# sensor_node4.net
KiCad netlist of a schematic drawn in EAGLE
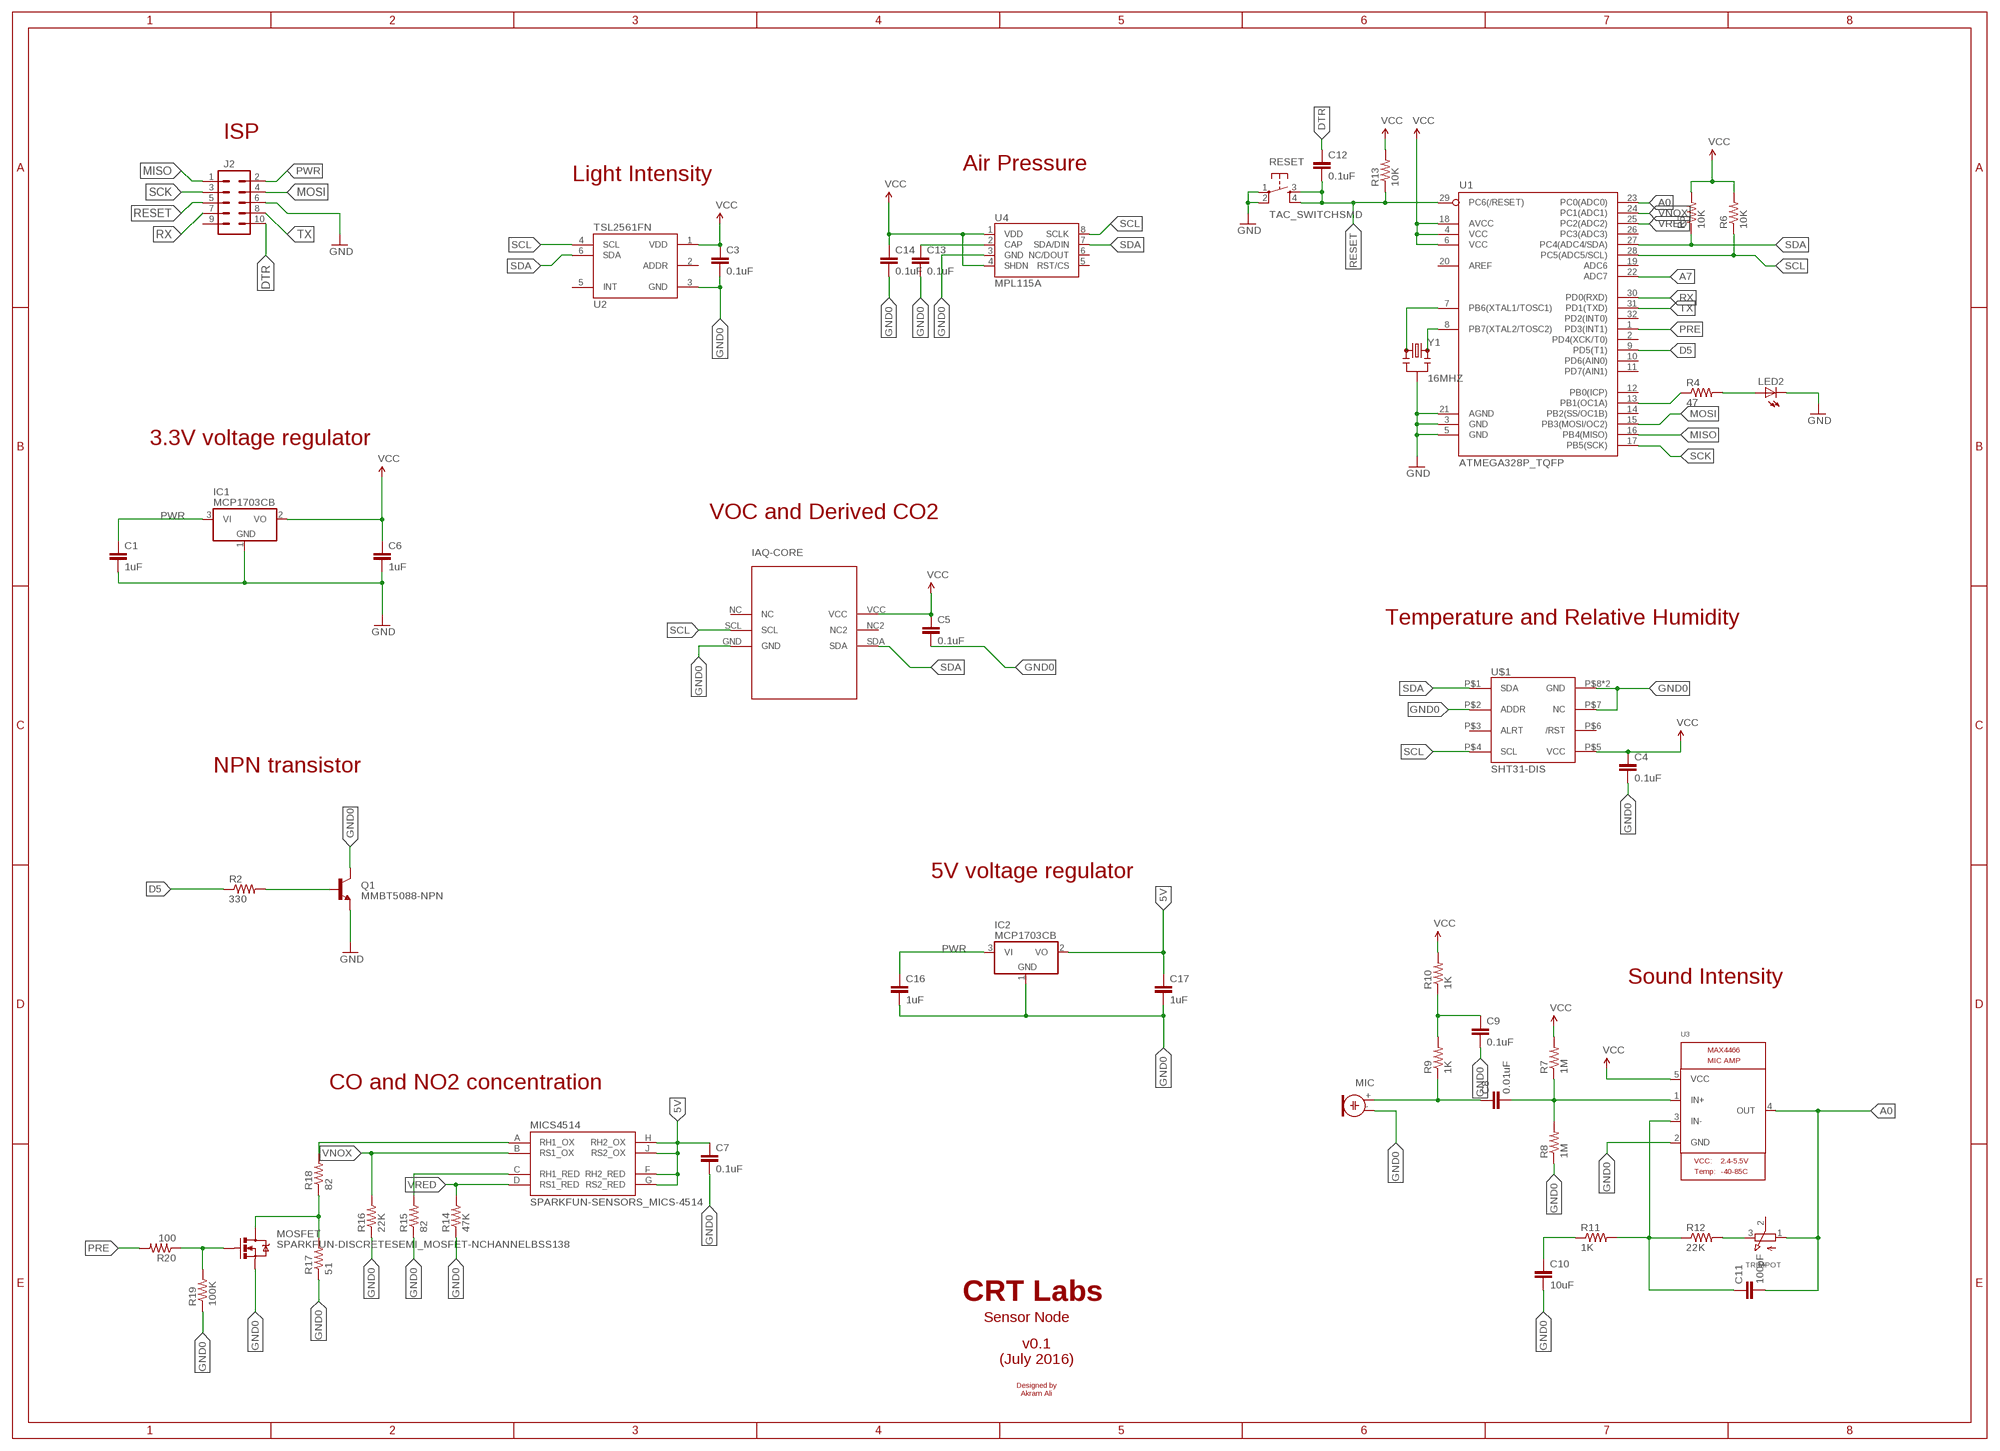
[diagram p0: schematic, sheet 1]

(export (version "E")
  (design (tool "Eeschema 10.0.6"))
  (components
    (comp (ref "C1")
      (value "1uF")
      (footprint "eagle-import:0805")
      (libsource (lib "eagle-import") (part "CAP0805"))
    )
    (comp (ref "C3")
      (value "0.1uF")
      (footprint "eagle-import:0805")
      (libsource (lib "eagle-import") (part "SparkFun-Passives_CAP0805"))
    )
    (comp (ref "C4")
      (value "0.1uF")
      (footprint "eagle-import:0805")
      (libsource (lib "eagle-import") (part "SparkFun-Passives_CAP0805"))
    )
    (comp (ref "C5")
      (value "0.1uF")
      (footprint "eagle-import:0805")
      (libsource (lib "eagle-import") (part "SparkFun-Passives_CAP0805"))
    )
    (comp (ref "C6")
      (value "1uF")
      (footprint "eagle-import:0805")
      (libsource (lib "eagle-import") (part "CAP0805"))
    )
    (comp (ref "C7")
      (value "0.1uF")
      (footprint "eagle-import:0805")
      (libsource (lib "eagle-import") (part "SparkFun-Passives_CAP0805"))
    )
    (comp (ref "C8")
      (value "0.01uF")
      (footprint "eagle-import:0805")
      (libsource (lib "eagle-import") (part "SparkFun-Passives_CAP0805"))
    )
    (comp (ref "C9")
      (value "0.1uF")
      (footprint "eagle-import:0805")
      (libsource (lib "eagle-import") (part "SparkFun-Passives_CAP0805"))
    )
    (comp (ref "C10")
      (value "10uF")
      (footprint "eagle-import:0805")
      (libsource (lib "eagle-import") (part "SparkFun-Passives_CAP0805"))
    )
    (comp (ref "C11")
      (value "100pF")
      (footprint "eagle-import:0805")
      (libsource (lib "eagle-import") (part "SparkFun-Passives_CAP0805"))
    )
    (comp (ref "C12")
      (value "0.1uF")
      (footprint "eagle-import:0805")
      (libsource (lib "eagle-import") (part "SparkFun-Passives_CAP0805"))
    )
    (comp (ref "C13")
      (value "0.1uF")
      (footprint "eagle-import:0805")
      (libsource (lib "eagle-import") (part "SparkFun-Passives_CAP0805"))
    )
    (comp (ref "C14")
      (value "0.1uF")
      (footprint "eagle-import:0805")
      (libsource (lib "eagle-import") (part "SparkFun-Passives_CAP0805"))
    )
    (comp (ref "C16")
      (value "1uF")
      (footprint "eagle-import:0805")
      (libsource (lib "eagle-import") (part "CAP0805"))
    )
    (comp (ref "C17")
      (value "1uF")
      (footprint "eagle-import:0805")
      (libsource (lib "eagle-import") (part "CAP0805"))
    )
    (comp (ref "IAQ-CORE")
      (value "IAQ-CORE")
      (footprint "eagle-import:IAQ-CORE")
      (fields (field (name "MPN") "IAQ CORE"))
      (libsource (lib "eagle-import") (part "IAQ-CORE"))
    )
    (comp (ref "IC1")
      (value "MCP1703CB")
      (footprint "eagle-import:SOT23")
      (fields (field (name "MPN") "MCP1703T-2502E/CB"))
      (libsource (lib "eagle-import") (part "MCP1703CB"))
    )
    (comp (ref "IC2")
      (value "MCP1703CB")
      (footprint "eagle-import:SOT23")
      (fields (field (name "MPN") "MCP1703T-2502E/CB"))
      (libsource (lib "eagle-import") (part "MCP1703CB"))
    )
    (comp (ref "J2")
      (value "M05X2PTH")
      (footprint "eagle-import:AVR_ICSP")
      (libsource (lib "eagle-import") (part "M05X2PTH"))
    )
    (comp (ref "LED2")
      (value "LEDCHIPLED_0805")
      (footprint "eagle-import:CHIPLED_0805")
      (libsource (lib "eagle-import") (part "LEDCHIPLED_0805"))
    )
    (comp (ref "MIC")
      (value "ELECTRET")
      (footprint "eagle-import:ELECTRET_9.7")
      (libsource (lib "eagle-import") (part "ELECTRET"))
    )
    (comp (ref "MICS4514")
      (value "SPARKFUN-SENSORS_MICS-4514")
      (footprint "eagle-import:SPARKFUN-SENSORS_MICS_10-SMD")
      (libsource (lib "eagle-import") (part "SPARKFUN-SENSORS_MICS-4514"))
    )
    (comp (ref "MOSFET")
      (value "SPARKFUN-DISCRETESEMI_MOSFET-NCHANNELBSS138")
      (footprint "eagle-import:SPARKFUN-DISCRETESEMI_SOT23-3")
      (libsource (lib "eagle-import") (part "SPARKFUN-DISCRETESEMI_MOSFET-NCHANNELBSS138"))
    )
    (comp (ref "Q1")
      (value "MMBT5088-NPN")
      (footprint "eagle-import:SOT23-3")
      (libsource (lib "eagle-import") (part "TRANSISTOR_NPNMMBT5088"))
    )
    (comp (ref "R2")
      (value "330")
      (footprint "eagle-import:0805")
      (libsource (lib "eagle-import") (part "RESISTOR0805-RES"))
    )
    (comp (ref "R4")
      (value "47")
      (footprint "eagle-import:0805")
      (libsource (lib "eagle-import") (part "SparkFun-Resistors_RESISTOR0805-RES"))
    )
    (comp (ref "R5")
      (value "10K")
      (footprint "eagle-import:0805")
      (libsource (lib "eagle-import") (part "SparkFun-Resistors_RESISTOR0805-RES"))
    )
    (comp (ref "R6")
      (value "10K")
      (footprint "eagle-import:0805")
      (libsource (lib "eagle-import") (part "SparkFun-Resistors_RESISTOR0805-RES"))
    )
    (comp (ref "R7")
      (value "1M")
      (footprint "eagle-import:0805")
      (libsource (lib "eagle-import") (part "RESISTOR0805-RES"))
    )
    (comp (ref "R8")
      (value "1M")
      (footprint "eagle-import:0805")
      (libsource (lib "eagle-import") (part "RESISTOR0805-RES"))
    )
    (comp (ref "R9")
      (value "1K")
      (footprint "eagle-import:0805")
      (libsource (lib "eagle-import") (part "RESISTOR0805-RES"))
    )
    (comp (ref "R10")
      (value "1K")
      (footprint "eagle-import:0805")
      (libsource (lib "eagle-import") (part "RESISTOR0805-RES"))
    )
    (comp (ref "R11")
      (value "1K")
      (footprint "eagle-import:0805")
      (libsource (lib "eagle-import") (part "RESISTOR0805-RES"))
    )
    (comp (ref "R12")
      (value "22K")
      (footprint "eagle-import:0805")
      (libsource (lib "eagle-import") (part "RESISTOR0805-RES"))
    )
    (comp (ref "R13")
      (value "10K")
      (footprint "eagle-import:0805")
      (libsource (lib "eagle-import") (part "RESISTOR0805-RES"))
    )
    (comp (ref "R14")
      (value "47K")
      (footprint "eagle-import:0805")
      (libsource (lib "eagle-import") (part "RESISTOR0805-RES"))
    )
    (comp (ref "R15")
      (value "82")
      (footprint "eagle-import:0805")
      (libsource (lib "eagle-import") (part "RESISTOR0805-RES"))
    )
    (comp (ref "R16")
      (value "22K")
      (footprint "eagle-import:0805")
      (libsource (lib "eagle-import") (part "RESISTOR0805-RES"))
    )
    (comp (ref "R17")
      (value "51")
      (footprint "eagle-import:0805")
      (libsource (lib "eagle-import") (part "RESISTOR0805-RES"))
    )
    (comp (ref "R18")
      (value "82")
      (footprint "eagle-import:0805")
      (libsource (lib "eagle-import") (part "RESISTOR0805-RES"))
    )
    (comp (ref "R19")
      (value "100K")
      (footprint "eagle-import:0805")
      (libsource (lib "eagle-import") (part "RESISTOR0805-RES"))
    )
    (comp (ref "R20")
      (value "100")
      (footprint "eagle-import:0805")
      (libsource (lib "eagle-import") (part "RESISTOR0805-RES"))
    )
    (comp (ref "RESET")
      (value "TAC_SWITCHSMD")
      (footprint "eagle-import:TACTILE-SWITCH-SMD")
      (libsource (lib "eagle-import") (part "TAC_SWITCHSMD"))
    )
    (comp (ref "TRIMPOT")
      (value "TRIMPOTTC33X-2")
      (footprint "eagle-import:TRIMPOT_BOURNS_TC33X-2")
      (libsource (lib "eagle-import") (part "TRIMPOTTC33X-2"))
    )
    (comp (ref "U$1")
      (value "SHT31-DIS")
      (footprint "eagle-import:SHT3X")
      (fields (field (name "MPN") "SHT31-DIS-B"))
      (libsource (lib "eagle-import") (part "SHT31-DIS"))
    )
    (comp (ref "U1")
      (value "ATMEGA328P_TQFP")
      (footprint "eagle-import:TQFP32-08")
      (fields (field (name "MPN") "ATMEGA328PB-AU"))
      (libsource (lib "eagle-import") (part "ATMEGA328P_TQFP"))
    )
    (comp (ref "U2")
      (value "TSL2561FN")
      (footprint "eagle-import:FN-6")
      (fields (field (name "MANF") "AMS-TAOS-USA-Inc."))
      (libsource (lib "eagle-import") (part "TSL2561FN"))
    )
    (comp (ref "U3")
      (value "MAX4466\"\"")
      (footprint "eagle-import:SC70-5")
      (fields (field (name "MPN") "MAX4466EXK+T"))
      (libsource (lib "eagle-import") (part "MAX4466{dblquote}{dblquote}"))
    )
    (comp (ref "U4")
      (value "MPL115A")
      (footprint "eagle-import:LGA8")
      (libsource (lib "eagle-import") (part "MPL115A"))
    )
    (comp (ref "Y1")
      (value "16MHZ")
      (footprint "eagle-import:RESONATOR-SMD")
      (libsource (lib "eagle-import") (part "RESONATOR16MHZ"))
    )
  )
  (nets
    (net (code "1") (name "5V") (class "Default")
      (node (ref "C17") (pin "1") (pinfunction "1_1") (pintype "passive"))
      (node (ref "C7") (pin "1") (pinfunction "1_1") (pintype "passive"))
      (node (ref "IC2") (pin "2") (pinfunction "VO_2") (pintype "passive"))
      (node (ref "MICS4514") (pin "F") (pinfunction "RH2_RED_F") (pintype "bidirectional"))
      (node (ref "MICS4514") (pin "G") (pinfunction "RS2_RED_G") (pintype "bidirectional"))
      (node (ref "MICS4514") (pin "H") (pinfunction "RH2_OX_H") (pintype "bidirectional"))
      (node (ref "MICS4514") (pin "J") (pinfunction "RS2_OX_J") (pintype "bidirectional"))
    )
    (net (code "2") (name "A0") (class "Default")
      (node (ref "C11") (pin "2") (pinfunction "2_2") (pintype "passive"))
      (node (ref "TRIMPOT") (pin "1") (pinfunction "A_1") (pintype "passive"))
      (node (ref "U1") (pin "23") (pinfunction "PC0(ADC0)_23") (pintype "bidirectional"))
      (node (ref "U3") (pin "4") (pinfunction "OUT_4") (pintype "bidirectional"))
    )
    (net (code "3") (name "A7") (class "Default")
      (node (ref "U1") (pin "22") (pinfunction "ADC7_22") (pintype "bidirectional"))
    )
    (net (code "4") (name "D5") (class "Default")
      (node (ref "R2") (pin "1") (pinfunction "1_1") (pintype "passive"))
      (node (ref "U1") (pin "9") (pinfunction "PD5(T1)_9") (pintype "bidirectional"))
    )
    (net (code "5") (name "DTR") (class "Default")
      (node (ref "C12") (pin "1") (pinfunction "1_1") (pintype "passive"))
      (node (ref "J2") (pin "10") (pinfunction "10_10") (pintype "passive"))
    )
    (net (code "6") (name "GND") (class "Default")
      (node (ref "C1") (pin "2") (pinfunction "2_2") (pintype "passive"))
      (node (ref "C6") (pin "2") (pinfunction "2_2") (pintype "passive"))
      (node (ref "IC1") (pin "1") (pinfunction "GND_1") (pintype "passive"))
      (node (ref "J2") (pin "6") (pinfunction "6_6") (pintype "passive"))
      (node (ref "LED2") (pin "C") (pinfunction "C_C") (pintype "passive"))
      (node (ref "Q1") (pin "2") (pinfunction "E_2") (pintype "passive"))
      (node (ref "RESET") (pin "1") (pinfunction "1_1") (pintype "passive"))
      (node (ref "RESET") (pin "2") (pinfunction "2_2") (pintype "passive"))
      (node (ref "U1") (pin "21") (pinfunction "AGND_21") (pintype "bidirectional"))
      (node (ref "U1") (pin "3") (pinfunction "GND_3") (pintype "bidirectional"))
      (node (ref "U1") (pin "5") (pinfunction "GND_5") (pintype "bidirectional"))
      (node (ref "Y1") (pin "2") (pinfunction "2_2") (pintype "passive"))
    )
    (net (code "7") (name "GND0") (class "Default")
      (node (ref "C10") (pin "2") (pinfunction "2_2") (pintype "passive"))
      (node (ref "C13") (pin "2") (pinfunction "2_2") (pintype "passive"))
      (node (ref "C14") (pin "2") (pinfunction "2_2") (pintype "passive"))
      (node (ref "C16") (pin "2") (pinfunction "2_2") (pintype "passive"))
      (node (ref "C17") (pin "2") (pinfunction "2_2") (pintype "passive"))
      (node (ref "C3") (pin "2") (pinfunction "2_2") (pintype "passive"))
      (node (ref "C4") (pin "2") (pinfunction "2_2") (pintype "passive"))
      (node (ref "C5") (pin "2") (pinfunction "2_2") (pintype "passive"))
      (node (ref "C7") (pin "2") (pinfunction "2_2") (pintype "passive"))
      (node (ref "C9") (pin "2") (pinfunction "2_2") (pintype "passive"))
      (node (ref "IAQ-CORE") (pin "GND") (pinfunction "GND_GND") (pintype "bidirectional"))
      (node (ref "IC2") (pin "1") (pinfunction "GND_1") (pintype "passive"))
      (node (ref "MIC") (pin "-") (pinfunction "1_-") (pintype "passive"))
      (node (ref "MOSFET") (pin "2") (pinfunction "S_2") (pintype "passive"))
      (node (ref "Q1") (pin "3") (pinfunction "C_3") (pintype "passive"))
      (node (ref "R14") (pin "1") (pinfunction "1_1") (pintype "passive"))
      (node (ref "R15") (pin "1") (pinfunction "1_1") (pintype "passive"))
      (node (ref "R16") (pin "1") (pinfunction "1_1") (pintype "passive"))
      (node (ref "R17") (pin "1") (pinfunction "1_1") (pintype "passive"))
      (node (ref "R19") (pin "1") (pinfunction "1_1") (pintype "passive"))
      (node (ref "R8") (pin "1") (pinfunction "1_1") (pintype "passive"))
      (node (ref "U$1") (pin "P$2") (pinfunction "ADDR_P$2") (pintype "bidirectional"))
      (node (ref "U$1") (pin "P$7") (pinfunction "NC_P$7") (pintype "bidirectional"))
      (node (ref "U$1") (pin "P$8") (pinfunction "GND_P$8") (pintype "bidirectional"))
      (node (ref "U$1") (pin "PAD") (pinfunction "GND_PAD") (pintype "bidirectional"))
      (node (ref "U2") (pin "3") (pinfunction "GND_3") (pintype "power_in"))
      (node (ref "U3") (pin "2") (pinfunction "GND_2") (pintype "bidirectional"))
      (node (ref "U4") (pin "3") (pinfunction "GND_3") (pintype "bidirectional"))
    )
    (net (code "8") (name "MISO") (class "Default")
      (node (ref "J2") (pin "1") (pinfunction "1_1") (pintype "passive"))
      (node (ref "U1") (pin "16") (pinfunction "PB4(MISO)_16") (pintype "bidirectional"))
    )
    (net (code "9") (name "MOSI") (class "Default")
      (node (ref "J2") (pin "4") (pinfunction "4_4") (pintype "passive"))
      (node (ref "U1") (pin "15") (pinfunction "PB3(MOSI/OC2)_15") (pintype "bidirectional"))
    )
    (net (code "10") (name "Net-(C9-Pad1)") (class "Default")
      (node (ref "C9") (pin "1") (pinfunction "1_1") (pintype "passive"))
      (node (ref "R10") (pin "1") (pinfunction "1_1") (pintype "passive"))
      (node (ref "R9") (pin "2") (pinfunction "2_2") (pintype "passive"))
    )
    (net (code "11") (name "Net-(C10-Pad1)") (class "Default")
      (node (ref "C10") (pin "1") (pinfunction "1_1") (pintype "passive"))
      (node (ref "R11") (pin "1") (pinfunction "1_1") (pintype "passive"))
    )
    (net (code "12") (name "Net-(LED2-PadA)") (class "Default")
      (node (ref "LED2") (pin "A") (pinfunction "A_A") (pintype "passive"))
      (node (ref "R4") (pin "2") (pinfunction "2_2") (pintype "passive"))
    )
    (net (code "13") (name "Net-(MIC-2)") (class "Default")
      (node (ref "C8") (pin "1") (pinfunction "1_1") (pintype "passive"))
      (node (ref "MIC") (pin "+") (pinfunction "2_+") (pintype "passive"))
      (node (ref "R9") (pin "1") (pinfunction "1_1") (pintype "passive"))
    )
    (net (code "14") (name "Net-(MICS4514-RH1_OX)") (class "Default")
      (node (ref "MICS4514") (pin "A") (pinfunction "RH1_OX_A") (pintype "bidirectional"))
      (node (ref "R18") (pin "2") (pinfunction "2_2") (pintype "passive"))
    )
    (net (code "15") (name "Net-(MICS4514-RH1_RED)") (class "Default")
      (node (ref "MICS4514") (pin "C") (pinfunction "RH1_RED_C") (pintype "bidirectional"))
      (node (ref "R15") (pin "2") (pinfunction "2_2") (pintype "passive"))
    )
    (net (code "16") (name "Net-(MOSFET-D)") (class "Default")
      (node (ref "MOSFET") (pin "3") (pinfunction "D_3") (pintype "passive"))
      (node (ref "R17") (pin "2") (pinfunction "2_2") (pintype "passive"))
      (node (ref "R18") (pin "1") (pinfunction "1_1") (pintype "passive"))
    )
    (net (code "17") (name "Net-(MOSFET-G)") (class "Default")
      (node (ref "MOSFET") (pin "1") (pinfunction "G_1") (pintype "passive"))
      (node (ref "R19") (pin "2") (pinfunction "2_2") (pintype "passive"))
      (node (ref "R20") (pin "1") (pinfunction "1_1") (pintype "passive"))
    )
    (net (code "18") (name "Net-(Q1-B)") (class "Default")
      (node (ref "Q1") (pin "1") (pinfunction "B_1") (pintype "passive"))
      (node (ref "R2") (pin "2") (pinfunction "2_2") (pintype "passive"))
    )
    (net (code "19") (name "Net-(TRIMPOT-E)") (class "Default")
      (node (ref "R12") (pin "2") (pinfunction "2_2") (pintype "passive"))
      (node (ref "TRIMPOT") (pin "3") (pinfunction "E_3") (pintype "passive"))
    )
    (net (code "20") (name "Net-(U1-PB1(OC1A))") (class "Default")
      (node (ref "R4") (pin "1") (pinfunction "1_1") (pintype "passive"))
      (node (ref "U1") (pin "13") (pinfunction "PB1(OC1A)_13") (pintype "bidirectional"))
    )
    (net (code "21") (name "Net-(U1-PB6(XTAL1{slash}TOSC1))") (class "Default")
      (node (ref "U1") (pin "7") (pinfunction "PB6(XTAL1/TOSC1)_7") (pintype "bidirectional"))
      (node (ref "Y1") (pin "1") (pinfunction "1_1") (pintype "passive"))
    )
    (net (code "22") (name "Net-(U1-PB7(XTAL2{slash}TOSC2))") (class "Default")
      (node (ref "U1") (pin "8") (pinfunction "PB7(XTAL2/TOSC2)_8") (pintype "bidirectional"))
      (node (ref "Y1") (pin "3") (pinfunction "3_3") (pintype "passive"))
    )
    (net (code "23") (name "Net-(U3-IN+)") (class "Default")
      (node (ref "C8") (pin "2") (pinfunction "2_2") (pintype "passive"))
      (node (ref "R7") (pin "1") (pinfunction "1_1") (pintype "passive"))
      (node (ref "R8") (pin "2") (pinfunction "2_2") (pintype "passive"))
      (node (ref "U3") (pin "1") (pinfunction "IN+_1") (pintype "bidirectional"))
    )
    (net (code "24") (name "Net-(U3-IN-)") (class "Default")
      (node (ref "C11") (pin "1") (pinfunction "1_1") (pintype "passive"))
      (node (ref "R11") (pin "2") (pinfunction "2_2") (pintype "passive"))
      (node (ref "R12") (pin "1") (pinfunction "1_1") (pintype "passive"))
      (node (ref "U3") (pin "3") (pinfunction "IN-_3") (pintype "bidirectional"))
    )
    (net (code "25") (name "Net-(U4-CAP)") (class "Default")
      (node (ref "C13") (pin "1") (pinfunction "1_1") (pintype "passive"))
      (node (ref "U4") (pin "2") (pinfunction "CAP_2") (pintype "bidirectional"))
    )
    (net (code "26") (name "PRE") (class "Default")
      (node (ref "R20") (pin "2") (pinfunction "2_2") (pintype "passive"))
      (node (ref "U1") (pin "1") (pinfunction "PD3(INT1)_1") (pintype "bidirectional"))
    )
    (net (code "27") (name "PWR") (class "Default")
      (node (ref "C1") (pin "1") (pinfunction "1_1") (pintype "passive"))
      (node (ref "C16") (pin "1") (pinfunction "1_1") (pintype "passive"))
      (node (ref "IC1") (pin "3") (pinfunction "VI_3") (pintype "input"))
      (node (ref "IC2") (pin "3") (pinfunction "VI_3") (pintype "input"))
      (node (ref "J2") (pin "2") (pinfunction "2_2") (pintype "passive"))
    )
    (net (code "28") (name "RESET") (class "Default")
      (node (ref "C12") (pin "2") (pinfunction "2_2") (pintype "passive"))
      (node (ref "J2") (pin "5") (pinfunction "5_5") (pintype "passive"))
      (node (ref "R13") (pin "1") (pinfunction "1_1") (pintype "passive"))
      (node (ref "RESET") (pin "3") (pinfunction "3_3") (pintype "passive"))
      (node (ref "RESET") (pin "4") (pinfunction "4_4") (pintype "passive"))
      (node (ref "U1") (pin "29") (pinfunction "PC6(/RESET)_29") (pintype "bidirectional"))
    )
    (net (code "29") (name "RX") (class "Default")
      (node (ref "J2") (pin "7") (pinfunction "7_7") (pintype "passive"))
      (node (ref "U1") (pin "30") (pinfunction "PD0(RXD)_30") (pintype "bidirectional"))
    )
    (net (code "30") (name "SCK") (class "Default")
      (node (ref "J2") (pin "3") (pinfunction "3_3") (pintype "passive"))
      (node (ref "U1") (pin "17") (pinfunction "PB5(SCK)_17") (pintype "bidirectional"))
    )
    (net (code "31") (name "SCL") (class "Default")
      (node (ref "IAQ-CORE") (pin "SCL") (pinfunction "SCL_SCL") (pintype "bidirectional"))
      (node (ref "R6") (pin "1") (pinfunction "1_1") (pintype "passive"))
      (node (ref "U$1") (pin "P$4") (pinfunction "SCL_P$4") (pintype "bidirectional"))
      (node (ref "U1") (pin "28") (pinfunction "PC5(ADC5/SCL)_28") (pintype "bidirectional"))
      (node (ref "U2") (pin "4") (pinfunction "SCL_4") (pintype "input"))
      (node (ref "U4") (pin "8") (pinfunction "SCLK_8") (pintype "bidirectional"))
    )
    (net (code "32") (name "SDA") (class "Default")
      (node (ref "IAQ-CORE") (pin "SDA") (pinfunction "SDA_SDA") (pintype "bidirectional"))
      (node (ref "R5") (pin "1") (pinfunction "1_1") (pintype "passive"))
      (node (ref "U$1") (pin "P$1") (pinfunction "SDA_P$1") (pintype "bidirectional"))
      (node (ref "U1") (pin "27") (pinfunction "PC4(ADC4/SDA)_27") (pintype "bidirectional"))
      (node (ref "U2") (pin "6") (pinfunction "SDA_6") (pintype "bidirectional"))
      (node (ref "U4") (pin "7") (pinfunction "SDA/DIN_7") (pintype "bidirectional"))
    )
    (net (code "33") (name "TX") (class "Default")
      (node (ref "J2") (pin "8") (pinfunction "8_8") (pintype "passive"))
      (node (ref "U1") (pin "31") (pinfunction "PD1(TXD)_31") (pintype "bidirectional"))
    )
    (net (code "34") (name "VCC") (class "Default")
      (node (ref "C14") (pin "1") (pinfunction "1_1") (pintype "passive"))
      (node (ref "C3") (pin "1") (pinfunction "1_1") (pintype "passive"))
      (node (ref "C4") (pin "1") (pinfunction "1_1") (pintype "passive"))
      (node (ref "C5") (pin "1") (pinfunction "1_1") (pintype "passive"))
      (node (ref "C6") (pin "1") (pinfunction "1_1") (pintype "passive"))
      (node (ref "IAQ-CORE") (pin "VCC") (pinfunction "VCC_VCC") (pintype "bidirectional"))
      (node (ref "IC1") (pin "2") (pinfunction "VO_2") (pintype "passive"))
      (node (ref "R10") (pin "2") (pinfunction "2_2") (pintype "passive"))
      (node (ref "R13") (pin "2") (pinfunction "2_2") (pintype "passive"))
      (node (ref "R5") (pin "2") (pinfunction "2_2") (pintype "passive"))
      (node (ref "R6") (pin "2") (pinfunction "2_2") (pintype "passive"))
      (node (ref "R7") (pin "2") (pinfunction "2_2") (pintype "passive"))
      (node (ref "U$1") (pin "P$5") (pinfunction "VCC_P$5") (pintype "bidirectional"))
      (node (ref "U1") (pin "18") (pinfunction "AVCC_18") (pintype "bidirectional"))
      (node (ref "U1") (pin "4") (pinfunction "VCC_4") (pintype "bidirectional"))
      (node (ref "U1") (pin "6") (pinfunction "VCC_6") (pintype "bidirectional"))
      (node (ref "U2") (pin "1") (pinfunction "VDD_1") (pintype "power_in"))
      (node (ref "U3") (pin "5") (pinfunction "VCC_5") (pintype "bidirectional"))
      (node (ref "U4") (pin "1") (pinfunction "VDD_1") (pintype "bidirectional"))
      (node (ref "U4") (pin "4") (pinfunction "SHDN_4") (pintype "bidirectional"))
    )
    (net (code "35") (name "VNOX") (class "Default")
      (node (ref "MICS4514") (pin "B") (pinfunction "RS1_OX_B") (pintype "bidirectional"))
      (node (ref "R16") (pin "2") (pinfunction "2_2") (pintype "passive"))
      (node (ref "U1") (pin "24") (pinfunction "PC1(ADC1)_24") (pintype "bidirectional"))
    )
    (net (code "36") (name "VRED") (class "Default")
      (node (ref "MICS4514") (pin "D") (pinfunction "RS1_RED_D") (pintype "bidirectional"))
      (node (ref "R14") (pin "2") (pinfunction "2_2") (pintype "passive"))
      (node (ref "U1") (pin "25") (pinfunction "PC2(ADC2)_25") (pintype "bidirectional"))
    )
    (net (code "37") (name "unconnected-(IAQ-CORE-PadNC)") (class "Default")
      (node (ref "IAQ-CORE") (pin "NC") (pinfunction "NC_NC") (pintype "bidirectional"))
    )
    (net (code "38") (name "unconnected-(IAQ-CORE-PadNC2)") (class "Default")
      (node (ref "IAQ-CORE") (pin "NC2") (pinfunction "NC2_NC2") (pintype "bidirectional"))
    )
    (net (code "39") (name "unconnected-(J2-Pad9)") (class "Default")
      (node (ref "J2") (pin "9") (pinfunction "9_9") (pintype "passive"))
    )
    (net (code "40") (name "unconnected-(TRIMPOT-S-Pad2)") (class "Default")
      (node (ref "TRIMPOT") (pin "2") (pinfunction "S_2") (pintype "passive"))
    )
    (net (code "41") (name "unconnected-(U$1-ALRT-PadP$3)") (class "Default")
      (node (ref "U$1") (pin "P$3") (pinfunction "ALRT_P$3") (pintype "bidirectional"))
    )
    (net (code "42") (name "unconnected-(U$1-{slash}RST-PadP$6)") (class "Default")
      (node (ref "U$1") (pin "P$6") (pinfunction "/RST_P$6") (pintype "bidirectional"))
    )
    (net (code "43") (name "unconnected-(U1-ADC6-Pad19)") (class "Default")
      (node (ref "U1") (pin "19") (pinfunction "ADC6_19") (pintype "bidirectional"))
    )
    (net (code "44") (name "unconnected-(U1-AREF-Pad20)") (class "Default")
      (node (ref "U1") (pin "20") (pinfunction "AREF_20") (pintype "bidirectional"))
    )
    (net (code "45") (name "unconnected-(U1-PB0(ICP)-Pad12)") (class "Default")
      (node (ref "U1") (pin "12") (pinfunction "PB0(ICP)_12") (pintype "bidirectional"))
    )
    (net (code "46") (name "unconnected-(U1-PB2(SS{slash}OC1B)-Pad14)") (class "Default")
      (node (ref "U1") (pin "14") (pinfunction "PB2(SS/OC1B)_14") (pintype "bidirectional"))
    )
    (net (code "47") (name "unconnected-(U1-PC3(ADC3)-Pad26)") (class "Default")
      (node (ref "U1") (pin "26") (pinfunction "PC3(ADC3)_26") (pintype "bidirectional"))
    )
    (net (code "48") (name "unconnected-(U1-PD2(INT0)-Pad32)") (class "Default")
      (node (ref "U1") (pin "32") (pinfunction "PD2(INT0)_32") (pintype "bidirectional"))
    )
    (net (code "49") (name "unconnected-(U1-PD4(XCK{slash}T0)-Pad2)") (class "Default")
      (node (ref "U1") (pin "2") (pinfunction "PD4(XCK/T0)_2") (pintype "bidirectional"))
    )
    (net (code "50") (name "unconnected-(U1-PD6(AIN0)-Pad10)") (class "Default")
      (node (ref "U1") (pin "10") (pinfunction "PD6(AIN0)_10") (pintype "bidirectional"))
    )
    (net (code "51") (name "unconnected-(U1-PD7(AIN1)-Pad11)") (class "Default")
      (node (ref "U1") (pin "11") (pinfunction "PD7(AIN1)_11") (pintype "bidirectional"))
    )
    (net (code "52") (name "unconnected-(U2-ADDR-Pad2)") (class "Default")
      (node (ref "U2") (pin "2") (pinfunction "ADDR_2") (pintype "input"))
    )
    (net (code "53") (name "unconnected-(U2-INT-Pad5)") (class "Default")
      (node (ref "U2") (pin "5") (pinfunction "INT_5") (pintype "output"))
    )
    (net (code "54") (name "unconnected-(U4-NC{slash}DOUT-Pad6)") (class "Default")
      (node (ref "U4") (pin "6") (pinfunction "NC/DOUT_6") (pintype "bidirectional"))
    )
    (net (code "55") (name "unconnected-(U4-RST{slash}CS-Pad5)") (class "Default")
      (node (ref "U4") (pin "5") (pinfunction "RST/CS_5") (pintype "bidirectional"))
    )
  )
)
